# me433_2019_motorboard.net
KiCad netlist of a schematic drawn in EAGLE
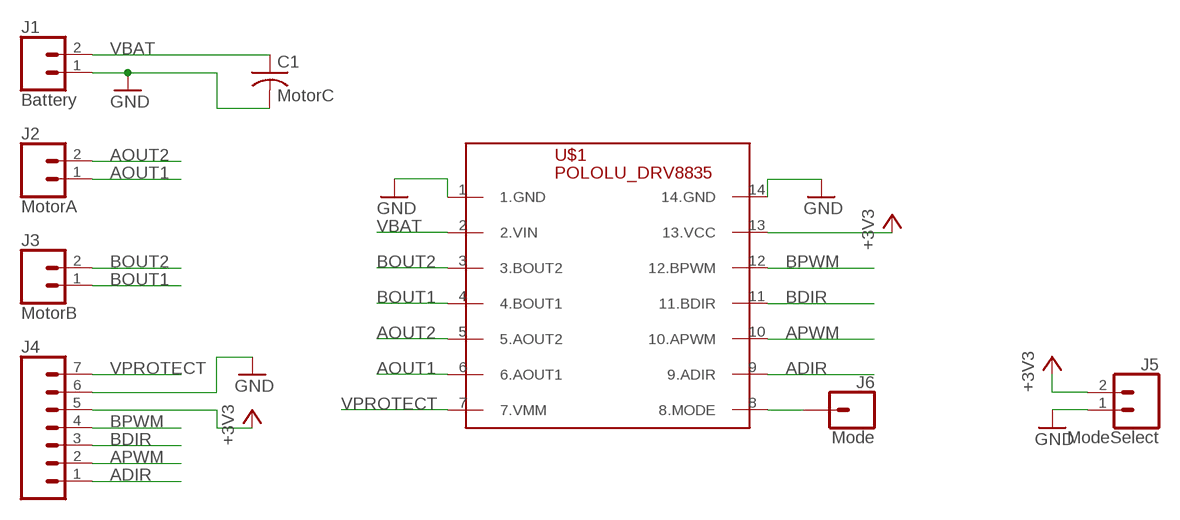
[diagram p0: schematic, sheet 1]

(export (version "E")
  (design (tool "Eeschema 10.0.6"))
  (components
    (comp (ref "C1")
      (value "MotorC")
      (footprint "eagle-import:C050-030X075")
      (libsource (lib "eagle-import") (part "C-US050-030X075"))
    )
    (comp (ref "J1")
      (value "Battery")
      (footprint "eagle-import:1X02")
      (libsource (lib "eagle-import") (part "CONN_02"))
    )
    (comp (ref "J2")
      (value "MotorA")
      (footprint "eagle-import:1X02")
      (libsource (lib "eagle-import") (part "CONN_02"))
    )
    (comp (ref "J3")
      (value "MotorB")
      (footprint "eagle-import:1X02")
      (libsource (lib "eagle-import") (part "CONN_02"))
    )
    (comp (ref "J4")
      (value "CONN_07")
      (footprint "eagle-import:1X07")
      (libsource (lib "eagle-import") (part "CONN_07"))
    )
    (comp (ref "J5")
      (value "ModeSelect")
      (footprint "eagle-import:1X02")
      (libsource (lib "eagle-import") (part "CONN_02"))
    )
    (comp (ref "J6")
      (value "Mode")
      (footprint "eagle-import:1X01")
      (libsource (lib "eagle-import") (part "CONN_01"))
    )
    (comp (ref "U$1")
      (value "POLOLU_DRV8835")
      (footprint "eagle-import:DIL14")
      (libsource (lib "eagle-import") (part "POLOLU_DRV8835"))
    )
  )
  (nets
    (net (code "1") (name "+3V3") (class "Default")
      (node (ref "J4") (pin "5") (pinfunction "5_5") (pintype "passive"))
      (node (ref "J5") (pin "2") (pinfunction "2_2") (pintype "passive"))
      (node (ref "U$1") (pin "13") (pinfunction "13.VCC_13") (pintype "bidirectional"))
    )
    (net (code "2") (name "/ADIR") (class "Default")
      (node (ref "J4") (pin "1") (pinfunction "1_1") (pintype "passive"))
      (node (ref "U$1") (pin "9") (pinfunction "9.ADIR_9") (pintype "bidirectional"))
    )
    (net (code "3") (name "/AOUT1") (class "Default")
      (node (ref "J2") (pin "1") (pinfunction "1_1") (pintype "passive"))
      (node (ref "U$1") (pin "6") (pinfunction "6.AOUT1_6") (pintype "bidirectional"))
    )
    (net (code "4") (name "/AOUT2") (class "Default")
      (node (ref "J2") (pin "2") (pinfunction "2_2") (pintype "passive"))
      (node (ref "U$1") (pin "5") (pinfunction "5.AOUT2_5") (pintype "bidirectional"))
    )
    (net (code "5") (name "/APWM") (class "Default")
      (node (ref "J4") (pin "2") (pinfunction "2_2") (pintype "passive"))
      (node (ref "U$1") (pin "10") (pinfunction "10.APWM_10") (pintype "bidirectional"))
    )
    (net (code "6") (name "/BDIR") (class "Default")
      (node (ref "J4") (pin "3") (pinfunction "3_3") (pintype "passive"))
      (node (ref "U$1") (pin "11") (pinfunction "11.BDIR_11") (pintype "bidirectional"))
    )
    (net (code "7") (name "/BOUT1") (class "Default")
      (node (ref "J3") (pin "1") (pinfunction "1_1") (pintype "passive"))
      (node (ref "U$1") (pin "4") (pinfunction "4.BOUT1_4") (pintype "bidirectional"))
    )
    (net (code "8") (name "/BOUT2") (class "Default")
      (node (ref "J3") (pin "2") (pinfunction "2_2") (pintype "passive"))
      (node (ref "U$1") (pin "3") (pinfunction "3.BOUT2_3") (pintype "bidirectional"))
    )
    (net (code "9") (name "/BPWM") (class "Default")
      (node (ref "J4") (pin "4") (pinfunction "4_4") (pintype "passive"))
      (node (ref "U$1") (pin "12") (pinfunction "12.BPWM_12") (pintype "bidirectional"))
    )
    (net (code "10") (name "/VBAT") (class "Default")
      (node (ref "C1") (pin "1") (pinfunction "1_1") (pintype "passive"))
      (node (ref "J1") (pin "2") (pinfunction "2_2") (pintype "passive"))
      (node (ref "U$1") (pin "2") (pinfunction "2.VIN_2") (pintype "bidirectional"))
    )
    (net (code "11") (name "/VPROTECT") (class "Default")
      (node (ref "J4") (pin "7") (pinfunction "7_7") (pintype "passive"))
      (node (ref "U$1") (pin "7") (pinfunction "7.VMM_7") (pintype "bidirectional"))
    )
    (net (code "12") (name "GND") (class "Default")
      (node (ref "C1") (pin "2") (pinfunction "2_2") (pintype "passive"))
      (node (ref "J1") (pin "1") (pinfunction "1_1") (pintype "passive"))
      (node (ref "J4") (pin "6") (pinfunction "6_6") (pintype "passive"))
      (node (ref "J5") (pin "1") (pinfunction "1_1") (pintype "passive"))
      (node (ref "U$1") (pin "1") (pinfunction "1.GND_1") (pintype "bidirectional"))
      (node (ref "U$1") (pin "14") (pinfunction "14.GND_14") (pintype "bidirectional"))
    )
    (net (code "13") (name "Net-(U$1-8.MODE)") (class "Default")
      (node (ref "J6") (pin "1") (pinfunction "1_1") (pintype "passive"))
      (node (ref "U$1") (pin "8") (pinfunction "8.MODE_8") (pintype "bidirectional"))
    )
  )
)
